# SCH_ZCD_TRIAC.net
KiCad netlist of a schematic drawn in Altium Designer
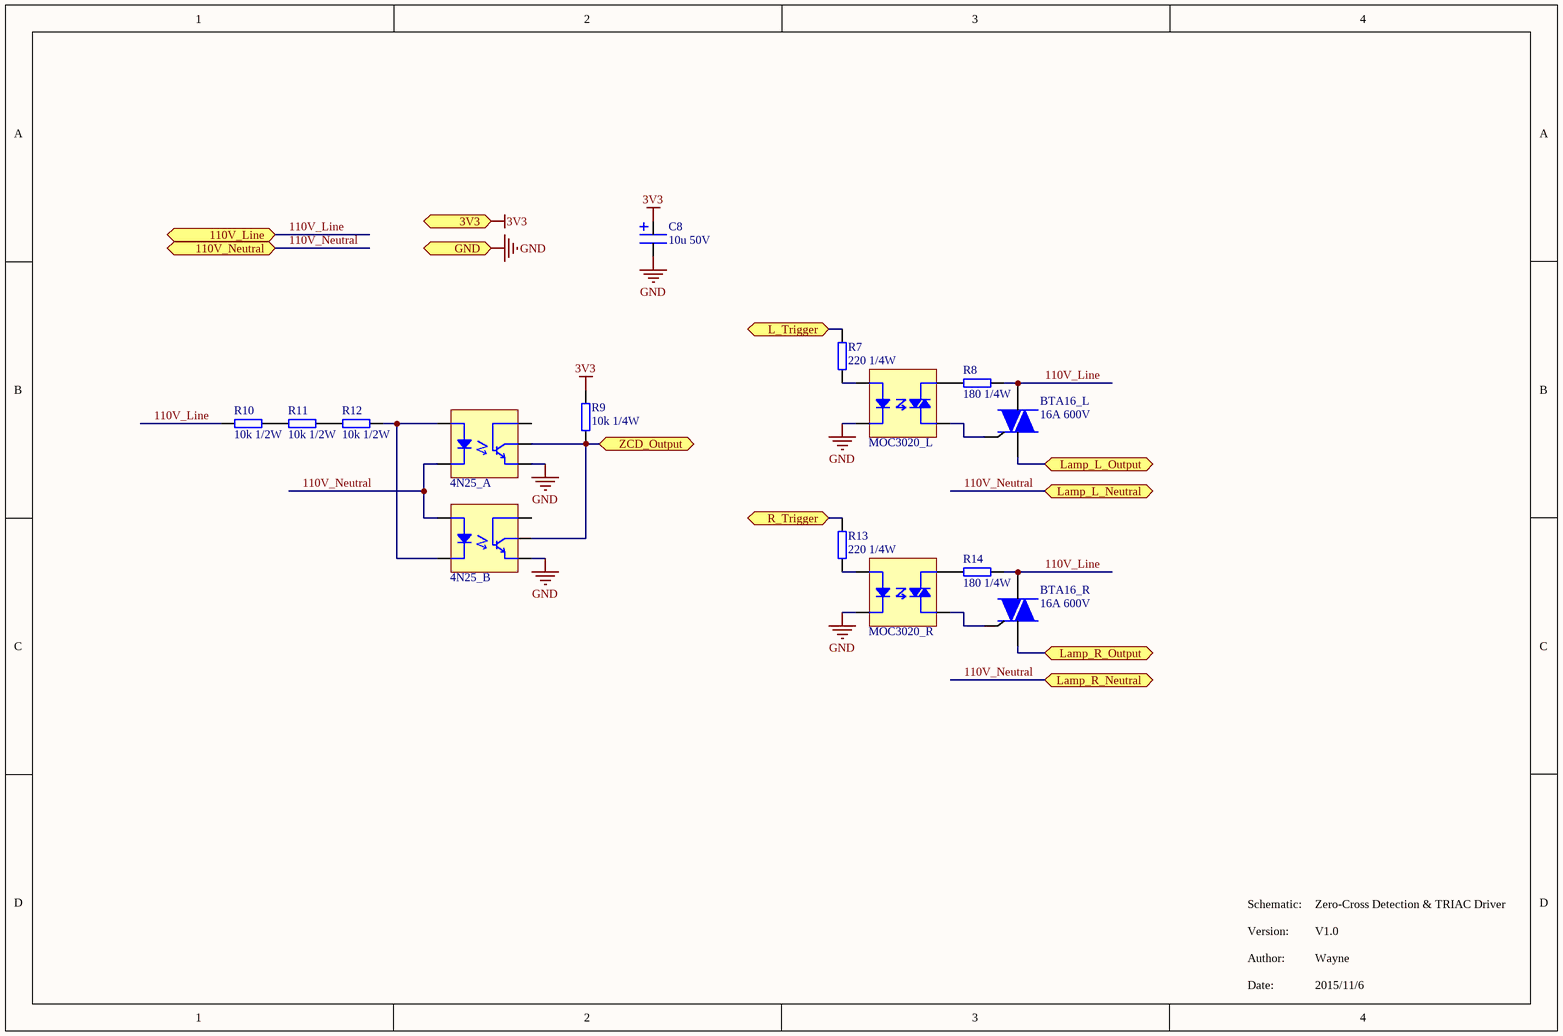
[diagram p0: SCH_ZCD_TRIAC.SchDoc]

(export (version "E")
  (design (tool "Eeschema 10.0.6"))
  (components
    (comp (ref "4N25_A")
      (value "4N25")
      (footprint "PCB_LIB:DIP6")
      (description "4N25 Opto Coupler")
      (libsource (lib "SCH_LIB") (part "4N25"))
    )
    (comp (ref "4N25_B")
      (value "4N25")
      (footprint "PCB_LIB:DIP6")
      (description "4N25 Opto Coupler")
      (libsource (lib "SCH_LIB") (part "4N25"))
    )
    (comp (ref "BTA16_L")
      (value "16A 600V")
      (footprint "PCB_LIB:TO220")
      (description "BTA16 Insulated TRIAC 16A")
      (fields (field (name "Comment") "BTA16"))
      (libsource (lib "SCH_LIB") (part "BTA16"))
    )
    (comp (ref "BTA16_R")
      (value "16A 600V")
      (footprint "PCB_LIB:TO220")
      (description "BTA16 Insulated TRIAC 16A")
      (fields (field (name "Comment") "BTA16"))
      (libsource (lib "SCH_LIB") (part "BTA16"))
    )
    (comp (ref "C8")
      (value "10u 50V")
      (footprint "PCB_LIB:CAP Axial 5mm")
      (description "Axial Cap")
      (fields (field (name "Comment") "Cap"))
      (libsource (lib "SCH_LIB") (part "Axial Cap"))
    )
    (comp (ref "MOC3020_L")
      (value "MOC3020")
      (footprint "PCB_LIB:DIP6")
      (description "MOC3020 Random Phase Triac Driver")
      (libsource (lib "SCH_LIB") (part "MOC3020"))
    )
    (comp (ref "MOC3020_R")
      (value "MOC3020")
      (footprint "PCB_LIB:DIP6")
      (description "MOC3020 Random Phase Triac Driver")
      (libsource (lib "SCH_LIB") (part "MOC3020"))
    )
    (comp (ref "R7")
      (value "220 1/4W")
      (footprint "PCB_LIB:1/4W Res")
      (description "Axial Resistor")
      (fields (field (name "Comment") "Res"))
      (libsource (lib "SCH_LIB") (part "Axial Resistor"))
    )
    (comp (ref "R8")
      (value "180 1/4W")
      (footprint "PCB_LIB:1/4W Res")
      (description "Axial Resistor")
      (fields (field (name "Comment") "Res"))
      (libsource (lib "SCH_LIB") (part "Axial Resistor"))
    )
    (comp (ref "R9")
      (value "10k 1/4W")
      (footprint "PCB_LIB:1/4W Res")
      (description "Axial Resistor")
      (fields (field (name "Comment") "Res"))
      (libsource (lib "SCH_LIB") (part "Axial Resistor"))
    )
    (comp (ref "R10")
      (value "10k 1/2W")
      (footprint "PCB_LIB:1/2W Res")
      (description "Axial Resistor")
      (fields (field (name "Comment") "Res"))
      (libsource (lib "SCH_LIB") (part "Axial Resistor"))
    )
    (comp (ref "R11")
      (value "10k 1/2W")
      (footprint "PCB_LIB:1/2W Res")
      (description "Axial Resistor")
      (fields (field (name "Comment") "Res"))
      (libsource (lib "SCH_LIB") (part "Axial Resistor"))
    )
    (comp (ref "R12")
      (value "10k 1/2W")
      (footprint "PCB_LIB:1/2W Res")
      (description "Axial Resistor")
      (fields (field (name "Comment") "Res"))
      (libsource (lib "SCH_LIB") (part "Axial Resistor"))
    )
    (comp (ref "R13")
      (value "220 1/4W")
      (footprint "PCB_LIB:1/4W Res")
      (description "Axial Resistor")
      (fields (field (name "Comment") "Res"))
      (libsource (lib "SCH_LIB") (part "Axial Resistor"))
    )
    (comp (ref "R14")
      (value "180 1/4W")
      (footprint "PCB_LIB:1/4W Res")
      (description "Axial Resistor")
      (fields (field (name "Comment") "Res"))
      (libsource (lib "SCH_LIB") (part "Axial Resistor"))
    )
  )
  (nets
    (net (code "1") (name "/110V_Line") (class "Default")
      (node (ref "BTA16_L") (pin "2") (pinfunction "A2_2") (pintype "passive"))
      (node (ref "BTA16_R") (pin "2") (pinfunction "A2_2") (pintype "passive"))
      (node (ref "R10") (pin "1") (pinfunction "1_1") (pintype "passive"))
      (node (ref "R14") (pin "1") (pinfunction "1_1") (pintype "passive"))
      (node (ref "R8") (pin "1") (pinfunction "1_1") (pintype "passive"))
    )
    (net (code "2") (name "/110V_Neutral") (class "Default")
      (node (ref "4N25_A") (pin "2") (pinfunction "CATHODE_2") (pintype "passive"))
      (node (ref "4N25_B") (pin "1") (pinfunction "ANODE_1") (pintype "passive"))
    )
    (net (code "3") (name "/L_Trigger") (class "Default")
      (node (ref "R7") (pin "2") (pinfunction "2_2") (pintype "passive"))
    )
    (net (code "4") (name "/Lamp_L_Output") (class "Default")
      (node (ref "BTA16_L") (pin "1") (pinfunction "A1_1") (pintype "passive"))
    )
    (net (code "5") (name "/Lamp_R_Output") (class "Default")
      (node (ref "BTA16_R") (pin "1") (pinfunction "A1_1") (pintype "passive"))
    )
    (net (code "6") (name "/R_Trigger") (class "Default")
      (node (ref "R13") (pin "2") (pinfunction "2_2") (pintype "passive"))
    )
    (net (code "7") (name "/ZCD_Output") (class "Default")
      (node (ref "4N25_A") (pin "5") (pinfunction "Collector_5") (pintype "passive"))
      (node (ref "4N25_B") (pin "5") (pinfunction "Collector_5") (pintype "passive"))
      (node (ref "R9") (pin "1") (pinfunction "1_1") (pintype "passive"))
    )
    (net (code "8") (name "3V3") (class "Default")
      (node (ref "C8") (pin "2") (pinfunction "2_2") (pintype "passive"))
      (node (ref "R9") (pin "2") (pinfunction "2_2") (pintype "passive"))
    )
    (net (code "9") (name "GND") (class "Default")
      (node (ref "4N25_A") (pin "4") (pinfunction "Emitter_4") (pintype "passive"))
      (node (ref "4N25_B") (pin "4") (pinfunction "Emitter_4") (pintype "passive"))
      (node (ref "C8") (pin "1") (pinfunction "1_1") (pintype "passive"))
      (node (ref "MOC3020_L") (pin "2") (pinfunction "CATHODE_2") (pintype "passive"))
      (node (ref "MOC3020_R") (pin "2") (pinfunction "CATHODE_2") (pintype "passive"))
    )
    (net (code "10") (name "Net-(4N25_A-ANODE)") (class "Default")
      (node (ref "4N25_A") (pin "1") (pinfunction "ANODE_1") (pintype "passive"))
      (node (ref "4N25_B") (pin "2") (pinfunction "CATHODE_2") (pintype "passive"))
      (node (ref "R12") (pin "2") (pinfunction "2_2") (pintype "passive"))
    )
    (net (code "11") (name "Net-(BTA16_L-G)") (class "Default")
      (node (ref "BTA16_L") (pin "3") (pinfunction "G_3") (pintype "passive"))
      (node (ref "MOC3020_L") (pin "4") (pinfunction "Term2_4") (pintype "passive"))
    )
    (net (code "12") (name "Net-(BTA16_R-G)") (class "Default")
      (node (ref "BTA16_R") (pin "3") (pinfunction "G_3") (pintype "passive"))
      (node (ref "MOC3020_R") (pin "4") (pinfunction "Term2_4") (pintype "passive"))
    )
    (net (code "13") (name "Net-(MOC3020_L-ANODE)") (class "Default")
      (node (ref "MOC3020_L") (pin "1") (pinfunction "ANODE_1") (pintype "passive"))
      (node (ref "R7") (pin "1") (pinfunction "1_1") (pintype "passive"))
    )
    (net (code "14") (name "Net-(MOC3020_L-Term1)") (class "Default")
      (node (ref "MOC3020_L") (pin "6") (pinfunction "Term1_6") (pintype "passive"))
      (node (ref "R8") (pin "2") (pinfunction "2_2") (pintype "passive"))
    )
    (net (code "15") (name "Net-(MOC3020_R-ANODE)") (class "Default")
      (node (ref "MOC3020_R") (pin "1") (pinfunction "ANODE_1") (pintype "passive"))
      (node (ref "R13") (pin "1") (pinfunction "1_1") (pintype "passive"))
    )
    (net (code "16") (name "Net-(MOC3020_R-Term1)") (class "Default")
      (node (ref "MOC3020_R") (pin "6") (pinfunction "Term1_6") (pintype "passive"))
      (node (ref "R14") (pin "2") (pinfunction "2_2") (pintype "passive"))
    )
    (net (code "17") (name "Net-(R10-Pad2)") (class "Default")
      (node (ref "R10") (pin "2") (pinfunction "2_2") (pintype "passive"))
      (node (ref "R11") (pin "1") (pinfunction "1_1") (pintype "passive"))
    )
    (net (code "18") (name "Net-(R11-Pad2)") (class "Default")
      (node (ref "R11") (pin "2") (pinfunction "2_2") (pintype "passive"))
      (node (ref "R12") (pin "1") (pinfunction "1_1") (pintype "passive"))
    )
    (net (code "19") (name "unconnected-(4N25_A-Base-Pad6)") (class "Default")
      (node (ref "4N25_A") (pin "6") (pinfunction "Base_6") (pintype "passive"))
    )
    (net (code "20") (name "unconnected-(4N25_B-Base-Pad6)") (class "Default")
      (node (ref "4N25_B") (pin "6") (pinfunction "Base_6") (pintype "passive"))
    )
  )
)
